# SCH.net
KiCad netlist of a schematic drawn in EasyEDA
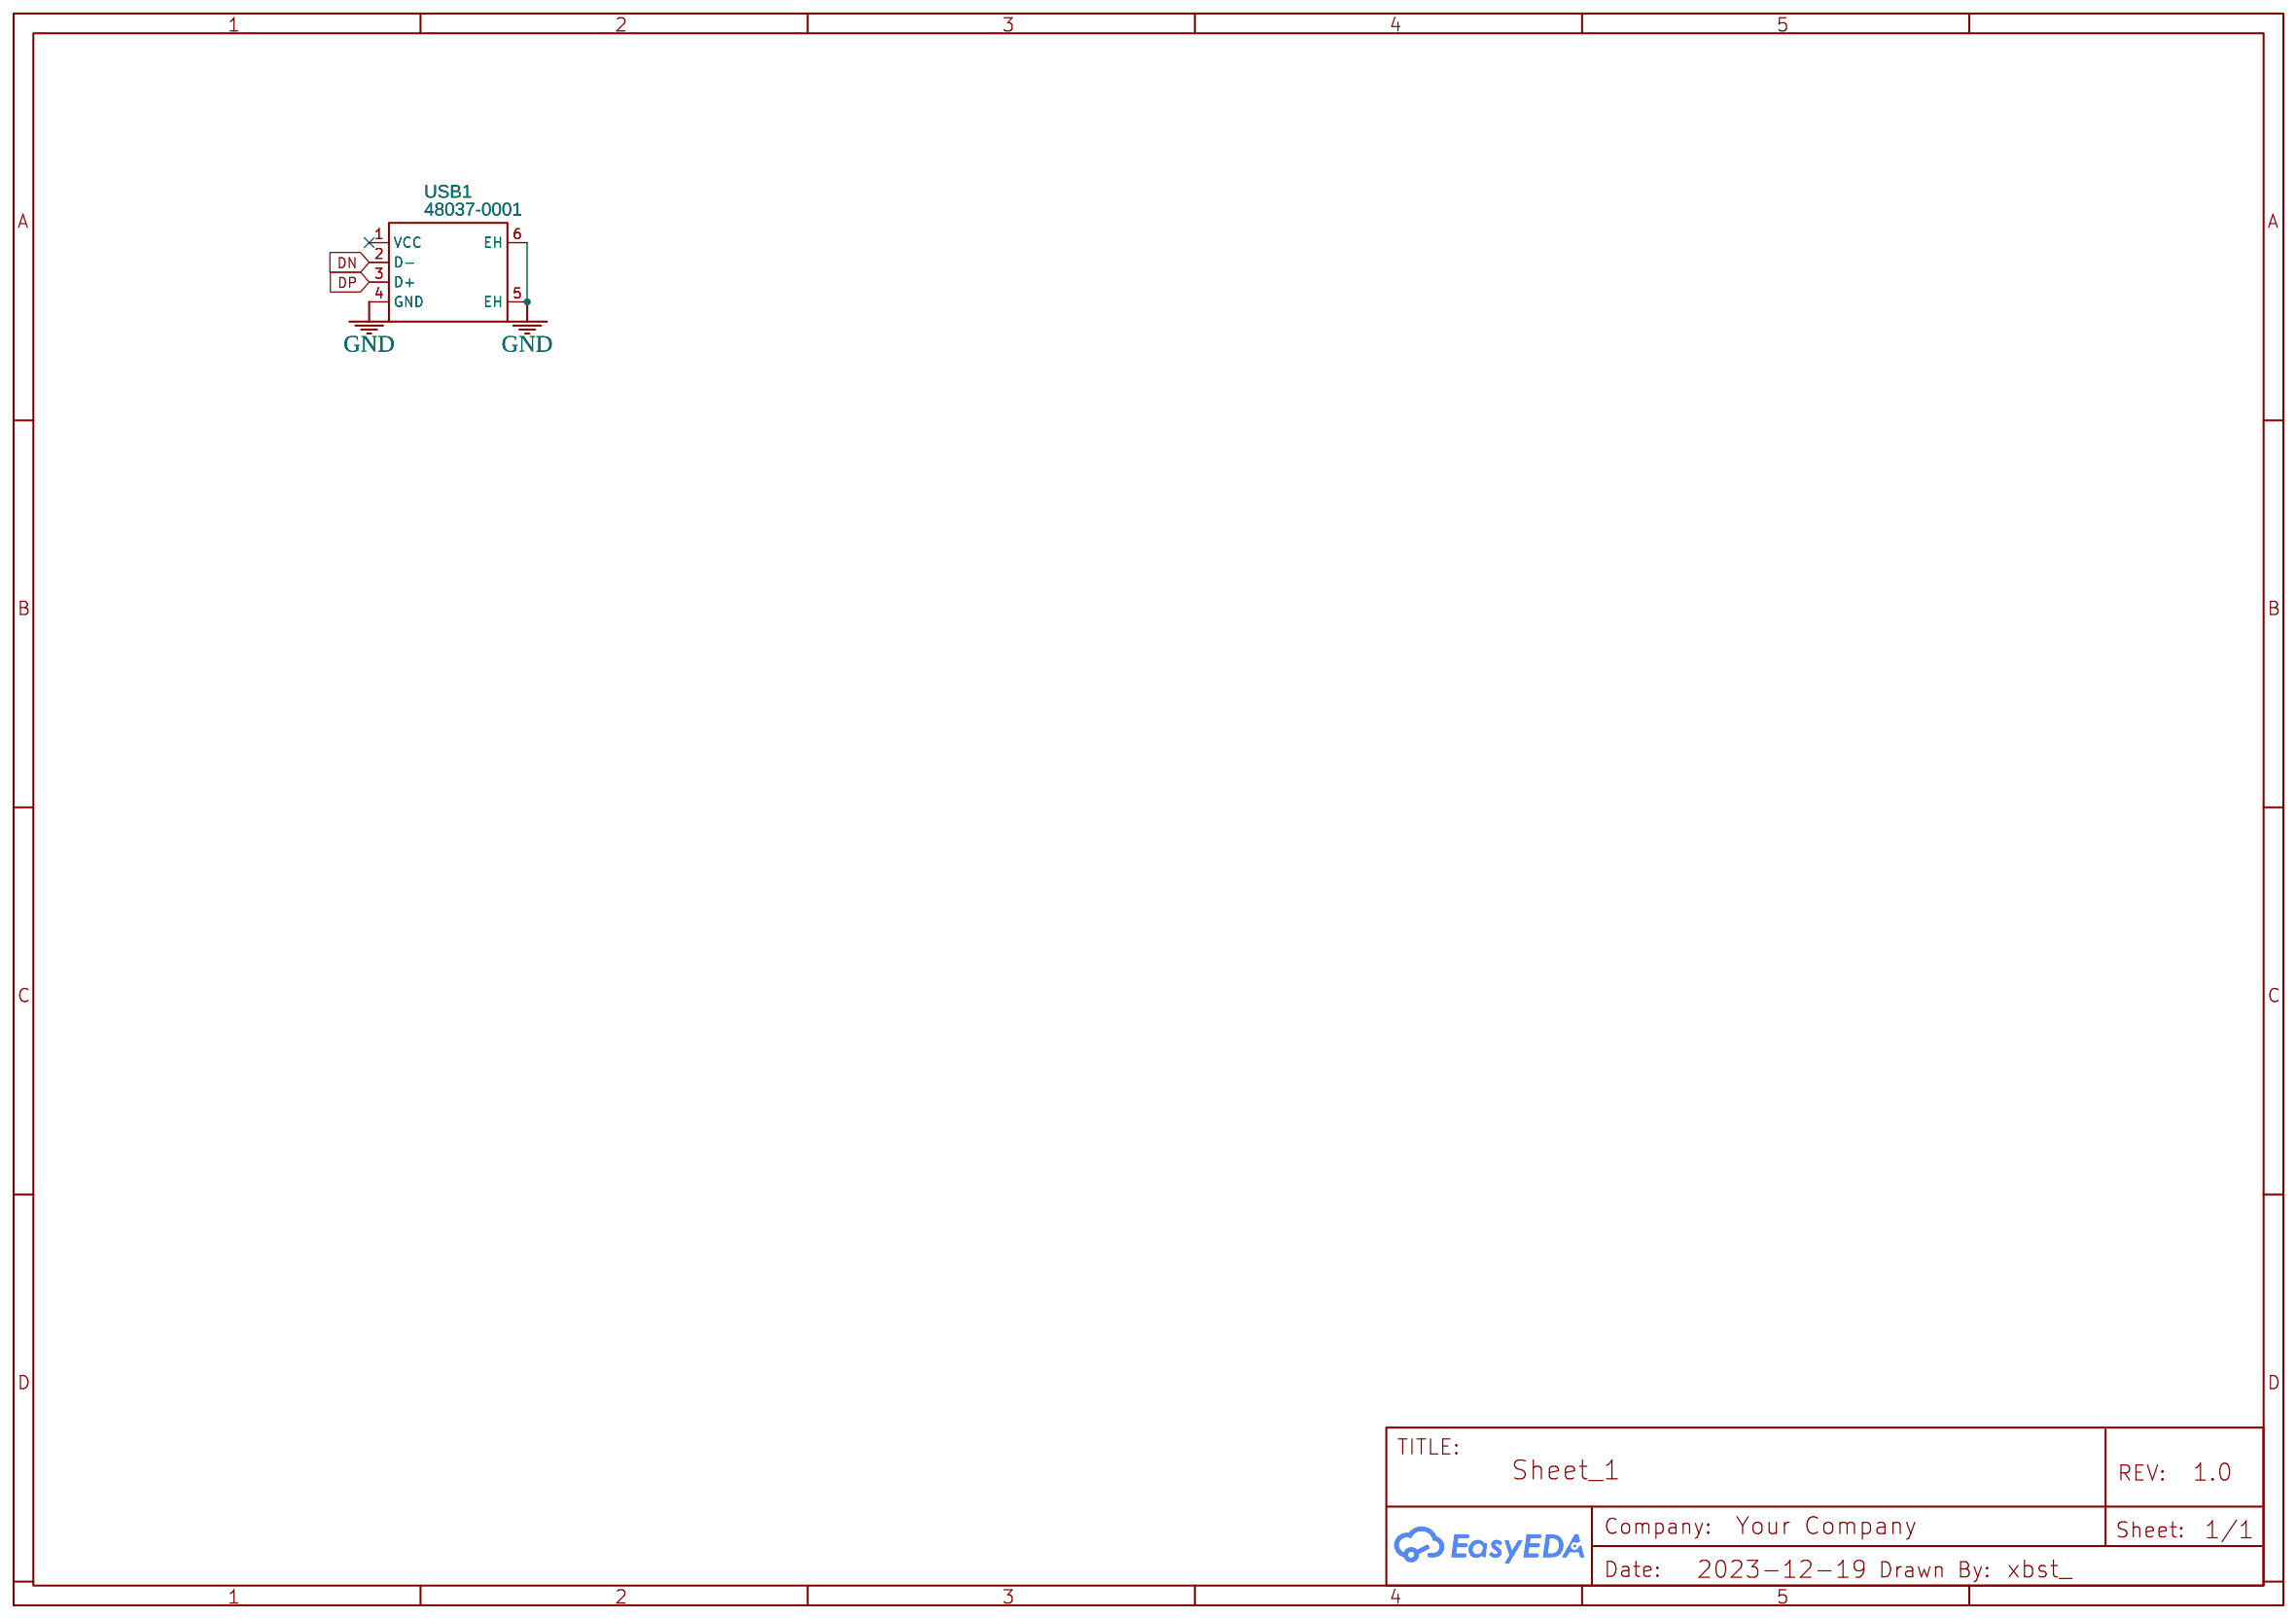
[diagram p0: schematic sheet]

(export (version "E")
  (design (tool "Eeschema 10.0.6"))
  (components
    (comp (ref "USB1")
      (value "48037-0001")
      (fields (field (name "Manufacturer Part") "480370001") (field (name "Manufacturer") "MOLEX"))
      (libsource (lib "") (part "48037-0001"))
    )
  )
  (nets
    (net (code "1") (name "DN") (class "Default")
      (node (ref "USB1") (pin "2") (pinfunction "D-_2") (pintype "input"))
    )
    (net (code "2") (name "DP") (class "Default")
      (node (ref "USB1") (pin "3") (pinfunction "D+_3") (pintype "input"))
    )
    (net (code "3") (name "GND") (class "Default")
      (node (ref "USB1") (pin "4") (pinfunction "GND_4") (pintype "input"))
      (node (ref "USB1") (pin "5") (pinfunction "EH_5") (pintype "unspecified"))
      (node (ref "USB1") (pin "6") (pinfunction "EH_6") (pintype "unspecified"))
    )
    (net (code "4") (name "unconnected-(USB1-VCC-Pad1)") (class "Default")
      (node (ref "USB1") (pin "1") (pinfunction "VCC_1") (pintype "input+no_connect"))
    )
  )
)
